# BSPD_Schematic.net
KiCad netlist of a schematic drawn in EAGLE
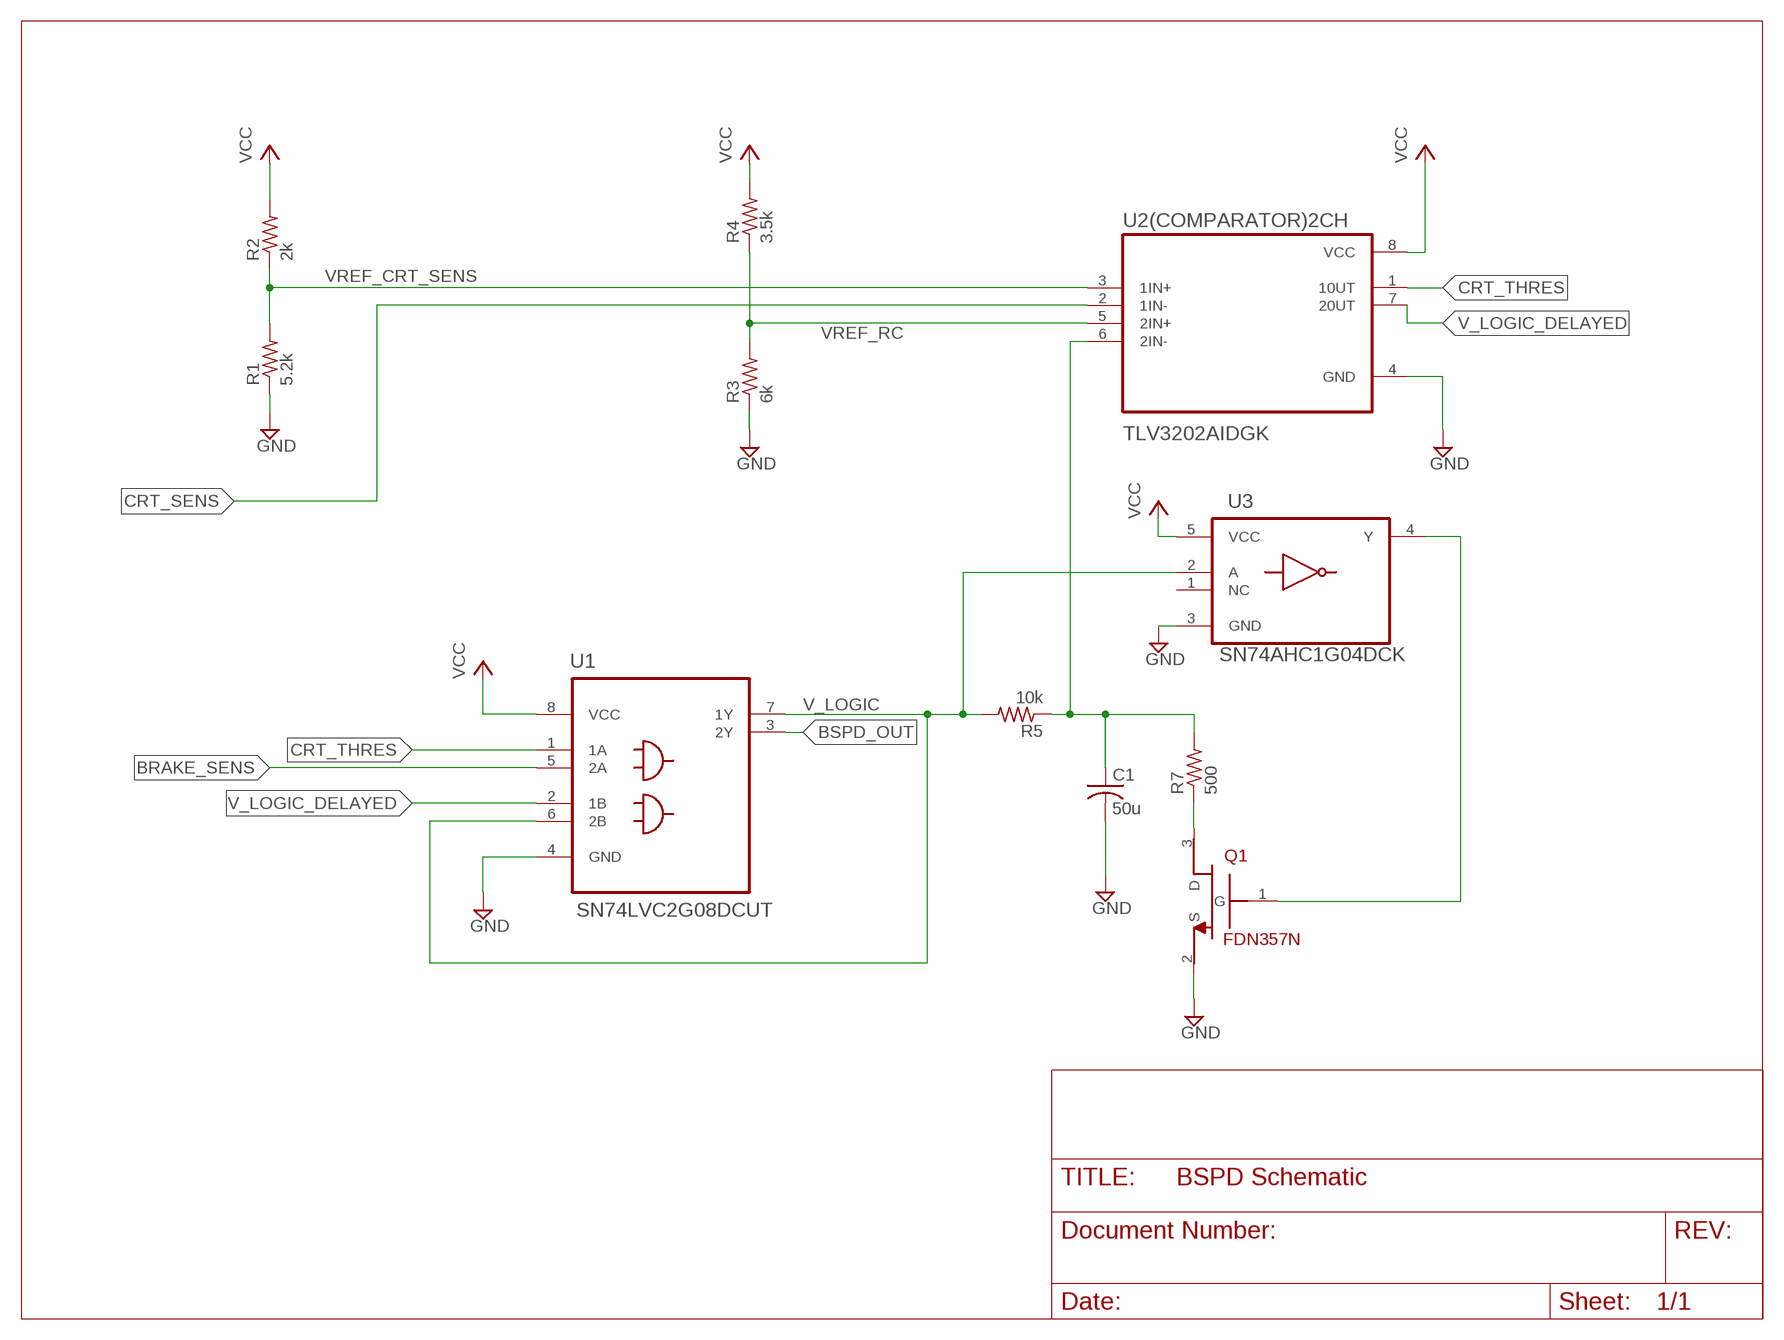
[diagram p0: schematic, sheet 1]

(export (version "E")
  (design (tool "Eeschema 10.0.6"))
  (components
    (comp (ref "C1")
      (value "50u")
      (footprint "eagle-import:C0603")
      (libsource (lib "eagle-import") (part "C-USC0603"))
    )
    (comp (ref "Q1")
      (value "FDN357N")
      (footprint "eagle-import:SOT95P280X130-3N")
      (libsource (lib "eagle-import") (part "FDN357N"))
    )
    (comp (ref "R1")
      (value "5.2k")
      (footprint "eagle-import:R0603")
      (libsource (lib "eagle-import") (part "R-US_R0603"))
    )
    (comp (ref "R2")
      (value "2k")
      (footprint "eagle-import:R0603")
      (libsource (lib "eagle-import") (part "R-US_R0603"))
    )
    (comp (ref "R3")
      (value "6k")
      (footprint "eagle-import:R0603")
      (libsource (lib "eagle-import") (part "R-US_R0603"))
    )
    (comp (ref "R4")
      (value "3.5k")
      (footprint "eagle-import:R0603")
      (libsource (lib "eagle-import") (part "R-US_R0603"))
    )
    (comp (ref "R5")
      (value "10k")
      (footprint "eagle-import:R0603")
      (libsource (lib "eagle-import") (part "R-US_R0603"))
    )
    (comp (ref "R7")
      (value "500")
      (footprint "eagle-import:R0603")
      (libsource (lib "eagle-import") (part "R-US_R0603"))
    )
    (comp (ref "U1")
      (value "SN74LVC2G08DCUT")
      (footprint "eagle-import:SOP50P310X90-8N")
      (fields (field (name "MF") "Texas Instruments"))
      (libsource (lib "eagle-import") (part "SN74LVC2G08DCUT"))
    )
    (comp (ref "U2(COMPARATOR)2CH")
      (value "TLV3202AIDGK")
      (footprint "eagle-import:SOP65P490X110-9N")
      (fields (field (name "MF") "Texas Instruments"))
      (libsource (lib "eagle-import") (part "TLV3202AIDGK"))
    )
    (comp (ref "U3")
      (value "SN74AHC1G04DCK")
      (footprint "eagle-import:SOT65P210X110-5N")
      (fields (field (name "MF") "Texas Instruments"))
      (libsource (lib "eagle-import") (part "SN74AHC1G04DCK"))
    )
  )
  (nets
    (net (code "1") (name "/VREF_CRT_SENS") (class "Default")
      (node (ref "R1") (pin "2") (pinfunction "2_2") (pintype "passive"))
      (node (ref "R2") (pin "1") (pinfunction "1_1") (pintype "passive"))
      (node (ref "U2(COMPARATOR)2CH") (pin "3") (pinfunction "1IN+_3") (pintype "input"))
    )
    (net (code "2") (name "/VREF_RC") (class "Default")
      (node (ref "R3") (pin "2") (pinfunction "2_2") (pintype "passive"))
      (node (ref "R4") (pin "1") (pinfunction "1_1") (pintype "passive"))
      (node (ref "U2(COMPARATOR)2CH") (pin "5") (pinfunction "2IN+_5") (pintype "input"))
    )
    (net (code "3") (name "/V_LOGIC") (class "Default")
      (node (ref "R5") (pin "2") (pinfunction "2_2") (pintype "passive"))
      (node (ref "U1") (pin "6") (pinfunction "2B_6") (pintype "input"))
      (node (ref "U1") (pin "7") (pinfunction "1Y_7") (pintype "output"))
      (node (ref "U3") (pin "2") (pinfunction "A_2") (pintype "input"))
    )
    (net (code "4") (name "BRAKE_SENS") (class "Default")
      (node (ref "U1") (pin "5") (pinfunction "2A_5") (pintype "input"))
    )
    (net (code "5") (name "BSPD_OUT") (class "Default")
      (node (ref "U1") (pin "3") (pinfunction "2Y_3") (pintype "output"))
    )
    (net (code "6") (name "CRT_SENS") (class "Default")
      (node (ref "U2(COMPARATOR)2CH") (pin "2") (pinfunction "1IN-_2") (pintype "input"))
    )
    (net (code "7") (name "CRT_THRES") (class "Default")
      (node (ref "U1") (pin "1") (pinfunction "1A_1") (pintype "input"))
      (node (ref "U2(COMPARATOR)2CH") (pin "1") (pinfunction "10UT_1") (pintype "output"))
    )
    (net (code "8") (name "GND") (class "Default")
      (node (ref "C1") (pin "2") (pinfunction "2_2") (pintype "passive"))
      (node (ref "Q1") (pin "2") (pinfunction "S_2") (pintype "bidirectional"))
      (node (ref "R1") (pin "1") (pinfunction "1_1") (pintype "passive"))
      (node (ref "R3") (pin "1") (pinfunction "1_1") (pintype "passive"))
      (node (ref "U1") (pin "4") (pinfunction "GND_4") (pintype "passive"))
      (node (ref "U2(COMPARATOR)2CH") (pin "4") (pinfunction "GND_4") (pintype "power_in"))
      (node (ref "U3") (pin "3") (pinfunction "GND_3") (pintype "passive"))
    )
    (net (code "9") (name "Net-(Q1-D)") (class "Default")
      (node (ref "Q1") (pin "3") (pinfunction "D_3") (pintype "bidirectional"))
      (node (ref "R7") (pin "1") (pinfunction "1_1") (pintype "passive"))
    )
    (net (code "10") (name "Net-(Q1-G)") (class "Default")
      (node (ref "Q1") (pin "1") (pinfunction "G_1") (pintype "input"))
      (node (ref "U3") (pin "4") (pinfunction "Y_4") (pintype "output"))
    )
    (net (code "11") (name "Net-(U2(COMPARATOR)2CH-2IN-)") (class "Default")
      (node (ref "C1") (pin "1") (pinfunction "1_1") (pintype "passive"))
      (node (ref "R5") (pin "1") (pinfunction "1_1") (pintype "passive"))
      (node (ref "R7") (pin "2") (pinfunction "2_2") (pintype "passive"))
      (node (ref "U2(COMPARATOR)2CH") (pin "6") (pinfunction "2IN-_6") (pintype "input"))
    )
    (net (code "12") (name "VCC") (class "Default")
      (node (ref "R2") (pin "2") (pinfunction "2_2") (pintype "passive"))
      (node (ref "R4") (pin "2") (pinfunction "2_2") (pintype "passive"))
      (node (ref "U1") (pin "8") (pinfunction "VCC_8") (pintype "power_in"))
      (node (ref "U2(COMPARATOR)2CH") (pin "8") (pinfunction "VCC_8") (pintype "power_in"))
      (node (ref "U3") (pin "5") (pinfunction "VCC_5") (pintype "power_in"))
    )
    (net (code "13") (name "V_LOGIC_DELAYED") (class "Default")
      (node (ref "U1") (pin "2") (pinfunction "1B_2") (pintype "input"))
      (node (ref "U2(COMPARATOR)2CH") (pin "7") (pinfunction "20UT_7") (pintype "output"))
    )
    (net (code "14") (name "unconnected-(U3-NC-Pad1)") (class "Default")
      (node (ref "U3") (pin "1") (pinfunction "NC_1") (pintype "no_connect"))
    )
  )
)
